# hd2.net
KiCad netlist of a schematic drawn in EAGLE
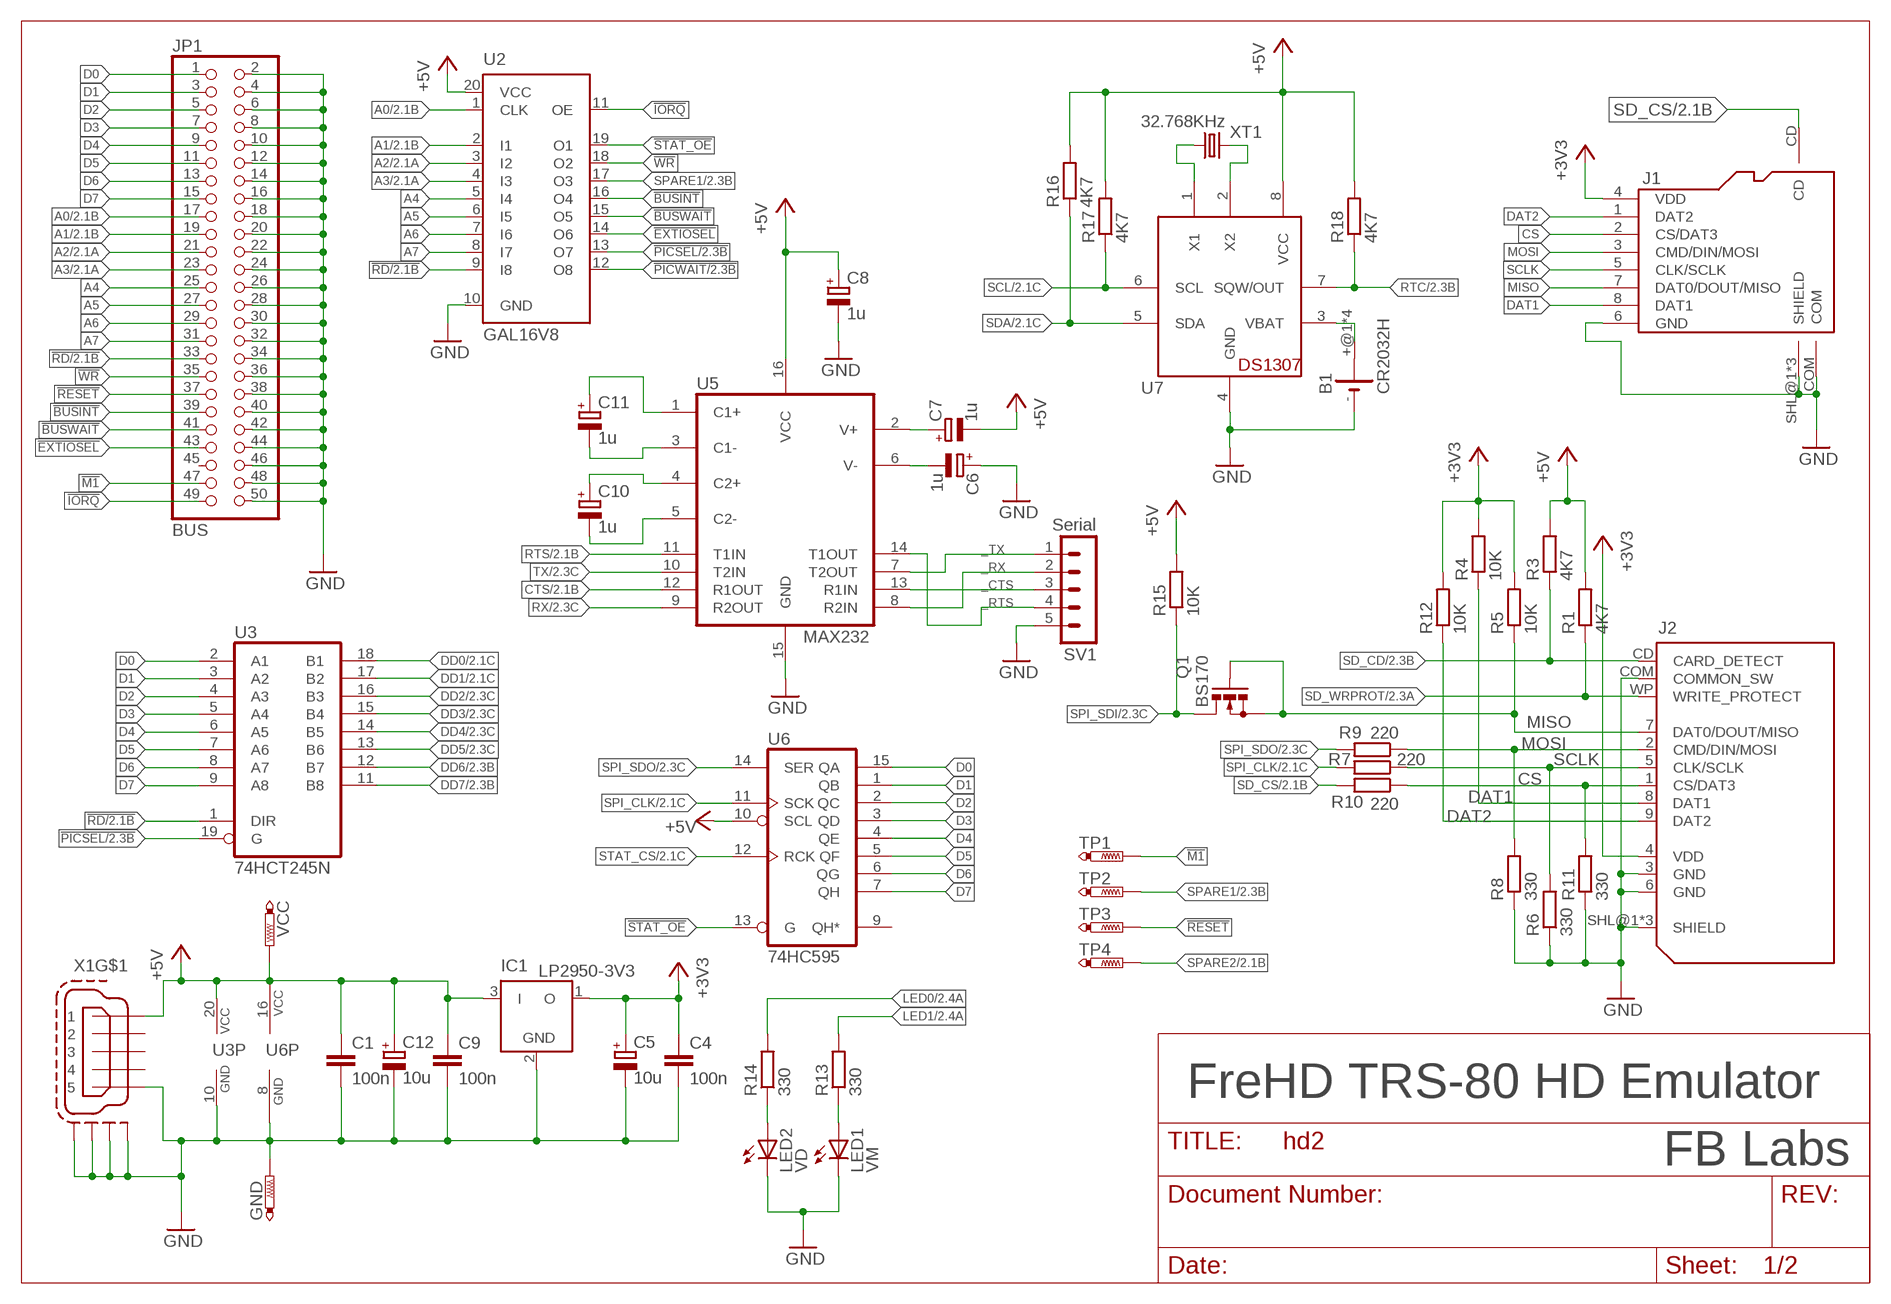
[diagram p0: schematic, sheet 1]
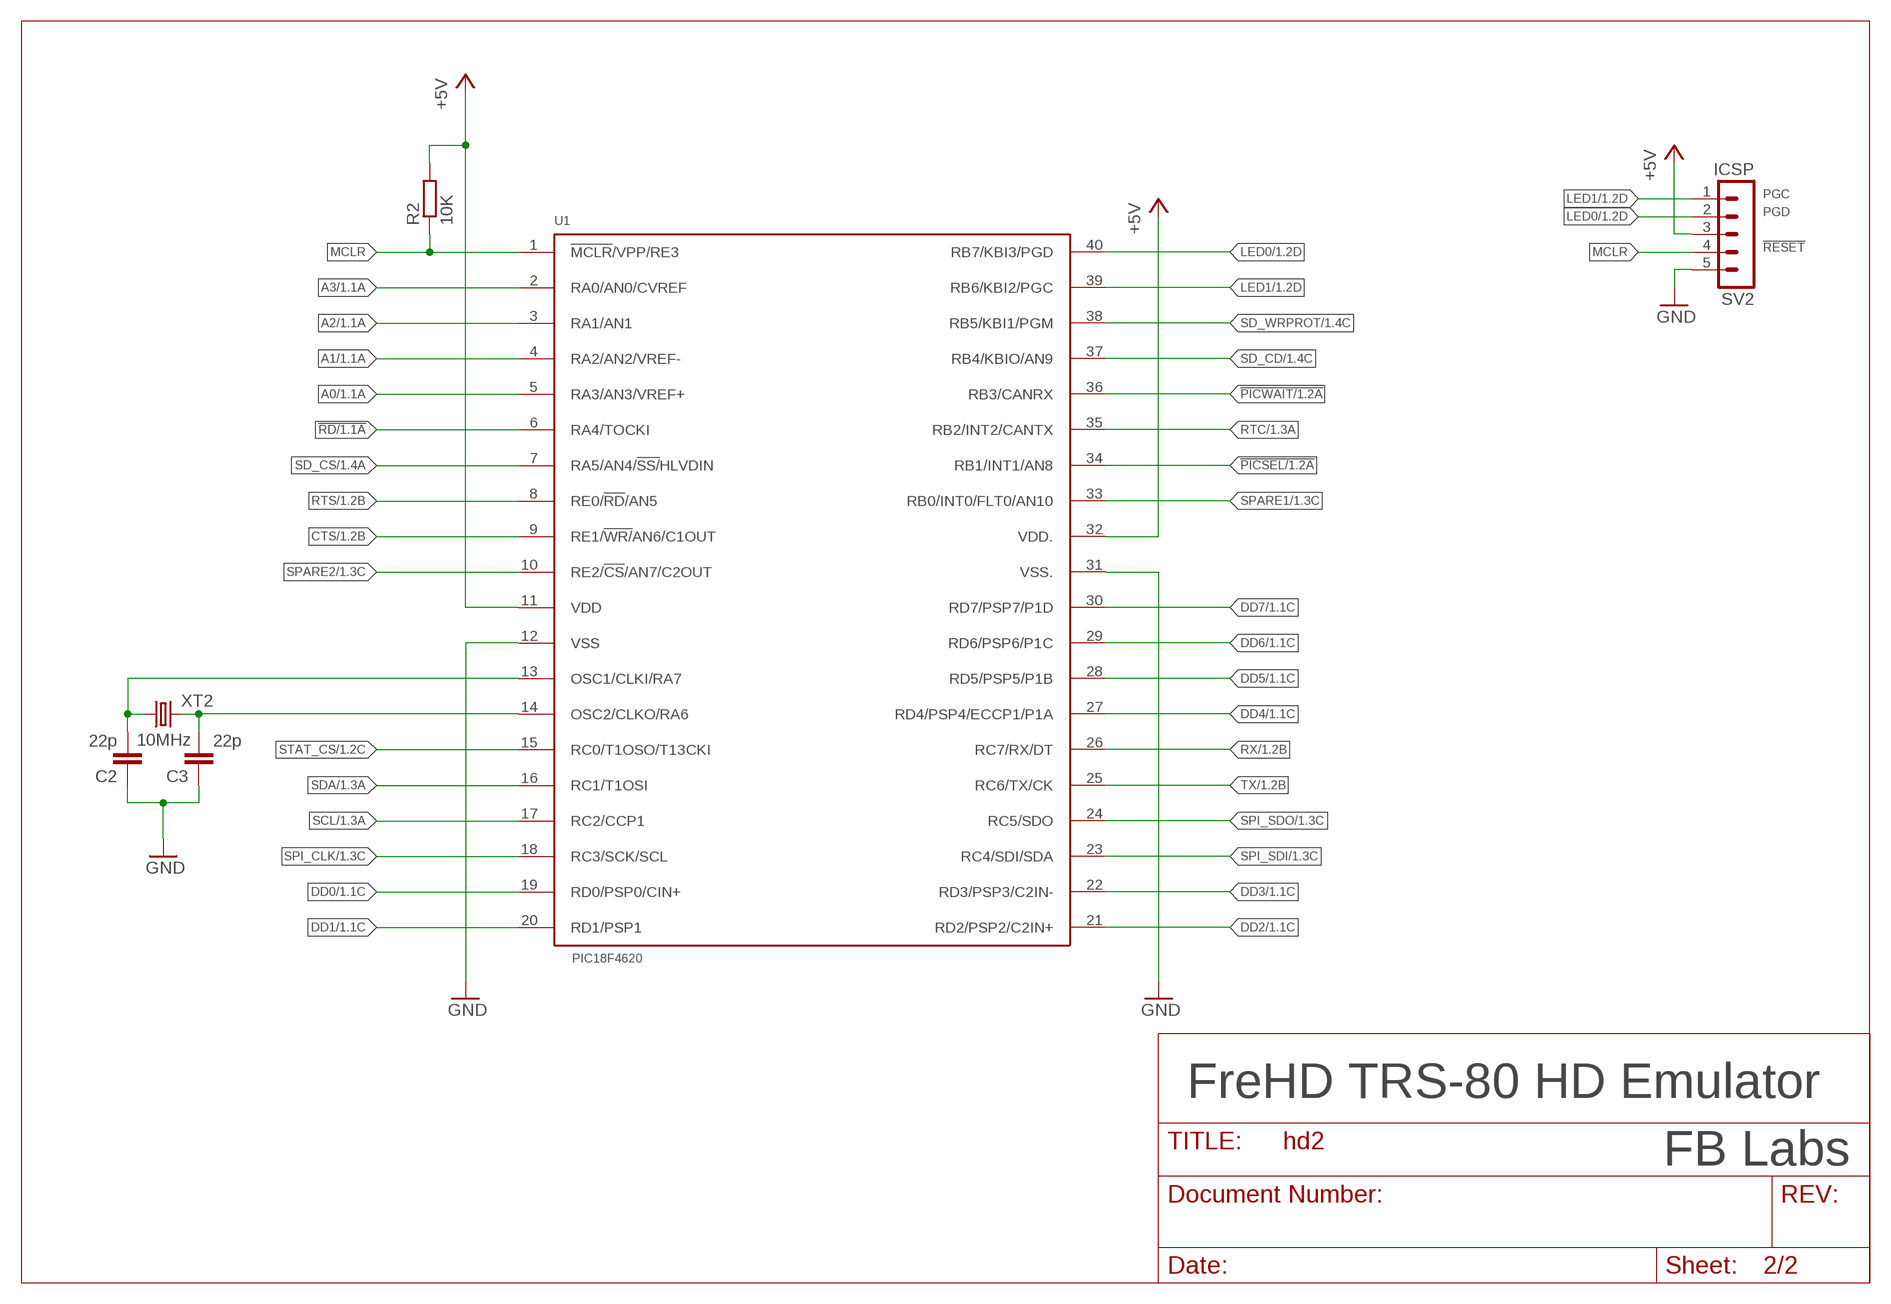
[diagram p1: schematic, sheet 2]

(export (version "E")
  (design (tool "Eeschema 10.0.6"))
  (components
    (comp (ref "B1")
      (value "CR2032H")
      (footprint "eagle-import:CR2032H")
      (libsource (lib "eagle-import") (part "CR2032H"))
    )
    (comp (ref "C1")
      (value "100n")
      (footprint "eagle-import:C050-024X044")
      (libsource (lib "eagle-import") (part "C-EU050-024X044"))
    )
    (comp (ref "C4")
      (value "100n")
      (footprint "eagle-import:C050-024X044")
      (libsource (lib "eagle-import") (part "C-EU050-024X044"))
    )
    (comp (ref "C5")
      (value "10u")
      (footprint "eagle-import:E2-4")
      (libsource (lib "eagle-import") (part "CPOL-EUE2-4"))
    )
    (comp (ref "C6")
      (value "1u")
      (footprint "eagle-import:E2-4")
      (libsource (lib "eagle-import") (part "CPOL-EUE2-4"))
    )
    (comp (ref "C7")
      (value "1u")
      (footprint "eagle-import:E2-4")
      (libsource (lib "eagle-import") (part "CPOL-EUE2-4"))
    )
    (comp (ref "C8")
      (value "1u")
      (footprint "eagle-import:E2-4")
      (libsource (lib "eagle-import") (part "CPOL-EUE2-4"))
    )
    (comp (ref "C9")
      (value "100n")
      (footprint "eagle-import:C050-024X044")
      (libsource (lib "eagle-import") (part "C-EU050-024X044"))
    )
    (comp (ref "C10")
      (value "1u")
      (footprint "eagle-import:E2-4")
      (libsource (lib "eagle-import") (part "CPOL-EUE2-4"))
    )
    (comp (ref "C11")
      (value "1u")
      (footprint "eagle-import:E2-4")
      (libsource (lib "eagle-import") (part "CPOL-EUE2-4"))
    )
    (comp (ref "C12")
      (value "10u")
      (footprint "eagle-import:E2-4")
      (libsource (lib "eagle-import") (part "CPOL-EUE2-4"))
    )
    (comp (ref "GND")
      (value "PTR1B2,54")
      (footprint "eagle-import:B2,54")
      (libsource (lib "eagle-import") (part "PTR1B2,54"))
    )
    (comp (ref "IC1")
      (value "LP2950-3V3")
      (footprint "eagle-import:TO92")
      (libsource (lib "eagle-import") (part "LP2950Z"))
    )
    (comp (ref "J1")
      (value "MICROSD-9P")
      (footprint "eagle-import:9P-SMD-W_-RING")
      (libsource (lib "eagle-import") (part "MICROSD-9P"))
    )
    (comp (ref "J2")
      (value "SDMMC06132")
      (footprint "eagle-import:06132")
      (libsource (lib "eagle-import") (part "SDMMC06132"))
    )
    (comp (ref "JP1")
      (value "BUS")
      (footprint "eagle-import:2X25")
      (libsource (lib "eagle-import") (part "PINHD-2X25"))
    )
    (comp (ref "LED1")
      (value "VM")
      (footprint "eagle-import:LED3MM")
      (libsource (lib "eagle-import") (part "LED3MM"))
    )
    (comp (ref "LED2")
      (value "VD")
      (footprint "eagle-import:LED3MM")
      (libsource (lib "eagle-import") (part "LED3MM"))
    )
    (comp (ref "Q1")
      (value "BS170")
      (footprint "eagle-import:SOT54E")
      (libsource (lib "eagle-import") (part "BS170"))
    )
    (comp (ref "R1")
      (value "4K7")
      (footprint "eagle-import:0207_10")
      (libsource (lib "eagle-import") (part "R-EU_0207/10"))
    )
    (comp (ref "R3")
      (value "4K7")
      (footprint "eagle-import:0207_10")
      (libsource (lib "eagle-import") (part "R-EU_0207/10"))
    )
    (comp (ref "R4")
      (value "10K")
      (footprint "eagle-import:0207_10")
      (libsource (lib "eagle-import") (part "R-EU_0207/10"))
    )
    (comp (ref "R5")
      (value "10K")
      (footprint "eagle-import:0207_10")
      (libsource (lib "eagle-import") (part "R-EU_0207/10"))
    )
    (comp (ref "R6")
      (value "330")
      (footprint "eagle-import:0207_10")
      (libsource (lib "eagle-import") (part "R-EU_0207/10"))
    )
    (comp (ref "R7")
      (value "220")
      (footprint "eagle-import:0207_10")
      (libsource (lib "eagle-import") (part "R-EU_0207/10"))
    )
    (comp (ref "R8")
      (value "330")
      (footprint "eagle-import:0207_10")
      (libsource (lib "eagle-import") (part "R-EU_0207/10"))
    )
    (comp (ref "R9")
      (value "220")
      (footprint "eagle-import:0207_10")
      (libsource (lib "eagle-import") (part "R-EU_0207/10"))
    )
    (comp (ref "R10")
      (value "220")
      (footprint "eagle-import:0207_10")
      (libsource (lib "eagle-import") (part "R-EU_0207/10"))
    )
    (comp (ref "R11")
      (value "330")
      (footprint "eagle-import:0207_10")
      (libsource (lib "eagle-import") (part "R-EU_0207/10"))
    )
    (comp (ref "R12")
      (value "10K")
      (footprint "eagle-import:0207_10")
      (libsource (lib "eagle-import") (part "R-EU_0207/10"))
    )
    (comp (ref "R13")
      (value "330")
      (footprint "eagle-import:0207_10")
      (libsource (lib "eagle-import") (part "R-EU_0207/10"))
    )
    (comp (ref "R14")
      (value "330")
      (footprint "eagle-import:0207_10")
      (libsource (lib "eagle-import") (part "R-EU_0207/10"))
    )
    (comp (ref "R15")
      (value "10K")
      (footprint "eagle-import:0207_10")
      (libsource (lib "eagle-import") (part "R-EU_0207/10"))
    )
    (comp (ref "R16")
      (value "4K7")
      (footprint "eagle-import:0207_10")
      (libsource (lib "eagle-import") (part "R-EU_0207/10"))
    )
    (comp (ref "R17")
      (value "4K7")
      (footprint "eagle-import:0207_10")
      (libsource (lib "eagle-import") (part "R-EU_0207/10"))
    )
    (comp (ref "R18")
      (value "4K7")
      (footprint "eagle-import:0207_10")
      (libsource (lib "eagle-import") (part "R-EU_0207/10"))
    )
    (comp (ref "SV1")
      (value "Serial")
      (footprint "eagle-import:MA05-1")
      (libsource (lib "eagle-import") (part "MA05-1"))
    )
    (comp (ref "TP1")
      (value "PTR1PAD1-10")
      (footprint "eagle-import:P1-10")
      (libsource (lib "eagle-import") (part "PTR1PAD1-10"))
    )
    (comp (ref "TP2")
      (value "PTR1PAD1-10")
      (footprint "eagle-import:P1-10")
      (libsource (lib "eagle-import") (part "PTR1PAD1-10"))
    )
    (comp (ref "TP3")
      (value "PTR1PAD1-10")
      (footprint "eagle-import:P1-10")
      (libsource (lib "eagle-import") (part "PTR1PAD1-10"))
    )
    (comp (ref "TP4")
      (value "PTR1PAD1-10")
      (footprint "eagle-import:P1-10")
      (libsource (lib "eagle-import") (part "PTR1PAD1-10"))
    )
    (comp (ref "U2")
      (value "GAL16V8")
      (footprint "eagle-import:DIL20")
      (fields (field (name "MPN") "ATF16V8CZ-15PU"))
      (libsource (lib "eagle-import") (part "ATF16V8BP3"))
    )
    (comp (ref "U3")
      (value "74HCT245N")
      (footprint "eagle-import:DIL20")
      (libsource (lib "eagle-import") (part "74245NHCT"))
    )
    (comp (ref "U5")
      (value "MAX232")
      (footprint "eagle-import:DIL16")
      (libsource (lib "eagle-import") (part "MAX232PTH"))
    )
    (comp (ref "U6")
      (value "74HC595")
      (footprint "eagle-import:DIL16")
      (libsource (lib "eagle-import") (part "74595NLS"))
    )
    (comp (ref "U7")
      (value "DS1307")
      (footprint "eagle-import:DIL08")
      (libsource (lib "eagle-import") (part "DS1307"))
    )
    (comp (ref "VCC")
      (value "PTR1B2,54")
      (footprint "eagle-import:B2,54")
      (libsource (lib "eagle-import") (part "PTR1B2,54"))
    )
    (comp (ref "X1")
      (value "MINI-USB-SCHIELD-32005-301")
      (footprint "eagle-import:32005-301")
      (libsource (lib "eagle-import") (part "MINI-USB-SCHIELD-32005-301"))
    )
    (comp (ref "XT1")
      (value "32.768KHz")
      (footprint "eagle-import:TC26V")
      (libsource (lib "eagle-import") (part "CRYSTALTC26V"))
    )
    (comp (ref "C2")
      (value "22p")
      (footprint "eagle-import:C050-024X044")
      (libsource (lib "eagle-import") (part "C-EU050-024X044"))
    )
    (comp (ref "C3")
      (value "22p")
      (footprint "eagle-import:C050-024X044")
      (libsource (lib "eagle-import") (part "C-EU050-024X044"))
    )
    (comp (ref "R2")
      (value "10K")
      (footprint "eagle-import:0207_10")
      (libsource (lib "eagle-import") (part "R-EU_0207/10"))
    )
    (comp (ref "SV2")
      (value "ICSP")
      (footprint "eagle-import:MA05-1")
      (libsource (lib "eagle-import") (part "MA05-1"))
    )
    (comp (ref "U1")
      (value "PIC18F4620")
      (footprint "eagle-import:PDIP-40")
      (libsource (lib "eagle-import") (part "PIC18F4680"))
    )
    (comp (ref "XT2")
      (value "10MHz")
      (footprint "eagle-import:HC49U-V")
      (libsource (lib "eagle-import") (part "CRYSTALHC49U-V"))
    )
  )
  (nets
    (net (code "1") (name "+3V3") (class "Default")
      (node (ref "C4") (pin "1") (pinfunction "1_1") (pintype "passive"))
      (node (ref "C5") (pin "+") (pinfunction "+_+") (pintype "passive"))
      (node (ref "IC1") (pin "1") (pinfunction "O_1") (pintype "input"))
      (node (ref "J1") (pin "4") (pinfunction "VDD_4") (pintype "power_in"))
      (node (ref "J2") (pin "4") (pinfunction "VDD_4") (pintype "power_in"))
      (node (ref "R12") (pin "2") (pinfunction "2_2") (pintype "passive"))
      (node (ref "R4") (pin "2") (pinfunction "2_2") (pintype "passive"))
      (node (ref "R5") (pin "2") (pinfunction "2_2") (pintype "passive"))
    )
    (net (code "2") (name "+5V") (class "Default")
      (node (ref "C1") (pin "1") (pinfunction "1_1") (pintype "passive"))
      (node (ref "C12") (pin "+") (pinfunction "+_+") (pintype "passive"))
      (node (ref "C7") (pin "-") (pinfunction "-_-") (pintype "passive"))
      (node (ref "C8") (pin "+") (pinfunction "+_+") (pintype "passive"))
      (node (ref "C9") (pin "1") (pinfunction "1_1") (pintype "passive"))
      (node (ref "IC1") (pin "3") (pinfunction "I_3") (pintype "input"))
      (node (ref "R1") (pin "2") (pinfunction "2_2") (pintype "passive"))
      (node (ref "R15") (pin "2") (pinfunction "2_2") (pintype "passive"))
      (node (ref "R16") (pin "2") (pinfunction "2_2") (pintype "passive"))
      (node (ref "R17") (pin "2") (pinfunction "2_2") (pintype "passive"))
      (node (ref "R18") (pin "2") (pinfunction "2_2") (pintype "passive"))
      (node (ref "R2") (pin "2") (pinfunction "2_2") (pintype "passive"))
      (node (ref "R3") (pin "2") (pinfunction "2_2") (pintype "passive"))
      (node (ref "SV2") (pin "3") (pinfunction "3_3") (pintype "passive"))
      (node (ref "U1") (pin "11") (pinfunction "VDD_11") (pintype "power_in"))
      (node (ref "U1") (pin "32") (pinfunction "VDD._32") (pintype "power_in"))
      (node (ref "U2") (pin "20") (pinfunction "VCC_20") (pintype "power_in"))
      (node (ref "U3") (pin "20") (pinfunction "VCC_20") (pintype "power_in"))
      (node (ref "U5") (pin "16") (pinfunction "VCC_16") (pintype "bidirectional"))
      (node (ref "U6") (pin "10") (pinfunction "SCL_10") (pintype "input"))
      (node (ref "U6") (pin "16") (pinfunction "VCC_16") (pintype "power_in"))
      (node (ref "U7") (pin "8") (pinfunction "VCC_8") (pintype "power_in"))
      (node (ref "VCC") (pin "TP") (pinfunction "TP_TP") (pintype "input"))
      (node (ref "X1") (pin "1") (pinfunction "1_1") (pintype "passive"))
    )
    (net (code "3") (name "A0") (class "Default")
      (node (ref "JP1") (pin "17") (pinfunction "17_17") (pintype "passive"))
      (node (ref "U1") (pin "5") (pinfunction "RA3/AN3/VREF+_5") (pintype "bidirectional"))
      (node (ref "U2") (pin "1") (pinfunction "CLK_1") (pintype "input"))
    )
    (net (code "4") (name "A1") (class "Default")
      (node (ref "JP1") (pin "19") (pinfunction "19_19") (pintype "passive"))
      (node (ref "U1") (pin "4") (pinfunction "RA2/AN2/VREF-_4") (pintype "bidirectional"))
      (node (ref "U2") (pin "2") (pinfunction "I1_2") (pintype "input"))
    )
    (net (code "5") (name "A2") (class "Default")
      (node (ref "JP1") (pin "21") (pinfunction "21_21") (pintype "passive"))
      (node (ref "U1") (pin "3") (pinfunction "RA1/AN1_3") (pintype "bidirectional"))
      (node (ref "U2") (pin "3") (pinfunction "I2_3") (pintype "input"))
    )
    (net (code "6") (name "A3") (class "Default")
      (node (ref "JP1") (pin "23") (pinfunction "23_23") (pintype "passive"))
      (node (ref "U1") (pin "2") (pinfunction "RA0/AN0/CVREF_2") (pintype "bidirectional"))
      (node (ref "U2") (pin "4") (pinfunction "I3_4") (pintype "input"))
    )
    (net (code "7") (name "A4") (class "Default")
      (node (ref "JP1") (pin "25") (pinfunction "25_25") (pintype "passive"))
      (node (ref "U2") (pin "5") (pinfunction "I4_5") (pintype "input"))
    )
    (net (code "8") (name "A5") (class "Default")
      (node (ref "JP1") (pin "27") (pinfunction "27_27") (pintype "passive"))
      (node (ref "U2") (pin "6") (pinfunction "I5_6") (pintype "input"))
    )
    (net (code "9") (name "A6") (class "Default")
      (node (ref "JP1") (pin "29") (pinfunction "29_29") (pintype "passive"))
      (node (ref "U2") (pin "7") (pinfunction "I6_7") (pintype "input"))
    )
    (net (code "10") (name "A7") (class "Default")
      (node (ref "JP1") (pin "31") (pinfunction "31_31") (pintype "passive"))
      (node (ref "U2") (pin "8") (pinfunction "I7_8") (pintype "input"))
    )
    (net (code "11") (name "CS") (class "Default")
      (node (ref "J1") (pin "2") (pinfunction "CS/DAT3_2") (pintype "input"))
      (node (ref "J2") (pin "1") (pinfunction "CS/DAT3_1") (pintype "input"))
      (node (ref "R10") (pin "1") (pinfunction "1_1") (pintype "passive"))
      (node (ref "R11") (pin "2") (pinfunction "2_2") (pintype "passive"))
    )
    (net (code "12") (name "CTS") (class "Default")
      (node (ref "U1") (pin "9") (pinfunction "RE1/~{WR/}AN6/C1OUT_9") (pintype "bidirectional"))
      (node (ref "U5") (pin "12") (pinfunction "R1OUT_12") (pintype "output"))
    )
    (net (code "13") (name "D0") (class "Default")
      (node (ref "JP1") (pin "1") (pinfunction "1_1") (pintype "passive"))
      (node (ref "U3") (pin "2") (pinfunction "A1_2") (pintype "bidirectional"))
      (node (ref "U6") (pin "15") (pinfunction "QA_15") (pintype "tri_state"))
    )
    (net (code "14") (name "D1") (class "Default")
      (node (ref "JP1") (pin "3") (pinfunction "3_3") (pintype "passive"))
      (node (ref "U3") (pin "3") (pinfunction "A2_3") (pintype "bidirectional"))
      (node (ref "U6") (pin "1") (pinfunction "QB_1") (pintype "tri_state"))
    )
    (net (code "15") (name "D2") (class "Default")
      (node (ref "JP1") (pin "5") (pinfunction "5_5") (pintype "passive"))
      (node (ref "U3") (pin "4") (pinfunction "A3_4") (pintype "bidirectional"))
      (node (ref "U6") (pin "2") (pinfunction "QC_2") (pintype "tri_state"))
    )
    (net (code "16") (name "D3") (class "Default")
      (node (ref "JP1") (pin "7") (pinfunction "7_7") (pintype "passive"))
      (node (ref "U3") (pin "5") (pinfunction "A4_5") (pintype "bidirectional"))
      (node (ref "U6") (pin "3") (pinfunction "QD_3") (pintype "tri_state"))
    )
    (net (code "17") (name "D4") (class "Default")
      (node (ref "JP1") (pin "9") (pinfunction "9_9") (pintype "passive"))
      (node (ref "U3") (pin "6") (pinfunction "A5_6") (pintype "bidirectional"))
      (node (ref "U6") (pin "4") (pinfunction "QE_4") (pintype "tri_state"))
    )
    (net (code "18") (name "D5") (class "Default")
      (node (ref "JP1") (pin "11") (pinfunction "11_11") (pintype "passive"))
      (node (ref "U3") (pin "7") (pinfunction "A6_7") (pintype "bidirectional"))
      (node (ref "U6") (pin "5") (pinfunction "QF_5") (pintype "tri_state"))
    )
    (net (code "19") (name "D6") (class "Default")
      (node (ref "JP1") (pin "13") (pinfunction "13_13") (pintype "passive"))
      (node (ref "U3") (pin "8") (pinfunction "A7_8") (pintype "bidirectional"))
      (node (ref "U6") (pin "6") (pinfunction "QG_6") (pintype "tri_state"))
    )
    (net (code "20") (name "D7") (class "Default")
      (node (ref "JP1") (pin "15") (pinfunction "15_15") (pintype "passive"))
      (node (ref "U3") (pin "9") (pinfunction "A8_9") (pintype "bidirectional"))
      (node (ref "U6") (pin "7") (pinfunction "QH_7") (pintype "tri_state"))
    )
    (net (code "21") (name "DAT1") (class "Default")
      (node (ref "J1") (pin "8") (pinfunction "DAT1_8") (pintype "bidirectional"))
      (node (ref "J2") (pin "8") (pinfunction "DAT1_8") (pintype "bidirectional"))
      (node (ref "R4") (pin "1") (pinfunction "1_1") (pintype "passive"))
    )
    (net (code "22") (name "DAT2") (class "Default")
      (node (ref "J1") (pin "1") (pinfunction "DAT2_1") (pintype "bidirectional"))
      (node (ref "J2") (pin "9") (pinfunction "DAT2_9") (pintype "bidirectional"))
      (node (ref "R12") (pin "1") (pinfunction "1_1") (pintype "passive"))
    )
    (net (code "23") (name "DD0") (class "Default")
      (node (ref "U1") (pin "19") (pinfunction "RD0/PSP0/CIN+_19") (pintype "bidirectional"))
      (node (ref "U3") (pin "18") (pinfunction "B1_18") (pintype "bidirectional"))
    )
    (net (code "24") (name "DD1") (class "Default")
      (node (ref "U1") (pin "20") (pinfunction "RD1/PSP1_20") (pintype "bidirectional"))
      (node (ref "U3") (pin "17") (pinfunction "B2_17") (pintype "bidirectional"))
    )
    (net (code "25") (name "DD2") (class "Default")
      (node (ref "U1") (pin "21") (pinfunction "RD2/PSP2/C2IN+_21") (pintype "bidirectional"))
      (node (ref "U3") (pin "16") (pinfunction "B3_16") (pintype "bidirectional"))
    )
    (net (code "26") (name "DD3") (class "Default")
      (node (ref "U1") (pin "22") (pinfunction "RD3/PSP3/C2IN-_22") (pintype "bidirectional"))
      (node (ref "U3") (pin "15") (pinfunction "B4_15") (pintype "bidirectional"))
    )
    (net (code "27") (name "DD4") (class "Default")
      (node (ref "U1") (pin "27") (pinfunction "RD4/PSP4/ECCP1/P1A_27") (pintype "bidirectional"))
      (node (ref "U3") (pin "14") (pinfunction "B5_14") (pintype "bidirectional"))
    )
    (net (code "28") (name "DD5") (class "Default")
      (node (ref "U1") (pin "28") (pinfunction "RD5/PSP5/P1B_28") (pintype "bidirectional"))
      (node (ref "U3") (pin "13") (pinfunction "B6_13") (pintype "bidirectional"))
    )
    (net (code "29") (name "DD6") (class "Default")
      (node (ref "U1") (pin "29") (pinfunction "RD6/PSP6/P1C_29") (pintype "bidirectional"))
      (node (ref "U3") (pin "12") (pinfunction "B7_12") (pintype "bidirectional"))
    )
    (net (code "30") (name "DD7") (class "Default")
      (node (ref "U1") (pin "30") (pinfunction "RD7/PSP7/P1D_30") (pintype "bidirectional"))
      (node (ref "U3") (pin "11") (pinfunction "B8_11") (pintype "bidirectional"))
    )
    (net (code "31") (name "GND") (class "Default")
      (node (ref "B1") (pin "-") (pinfunction "-_-") (pintype "passive"))
      (node (ref "C1") (pin "2") (pinfunction "2_2") (pintype "passive"))
      (node (ref "C12") (pin "-") (pinfunction "-_-") (pintype "passive"))
      (node (ref "C2") (pin "1") (pinfunction "1_1") (pintype "passive"))
      (node (ref "C3") (pin "1") (pinfunction "1_1") (pintype "passive"))
      (node (ref "C4") (pin "2") (pinfunction "2_2") (pintype "passive"))
      (node (ref "C5") (pin "-") (pinfunction "-_-") (pintype "passive"))
      (node (ref "C6") (pin "+") (pinfunction "+_+") (pintype "passive"))
      (node (ref "C8") (pin "-") (pinfunction "-_-") (pintype "passive"))
      (node (ref "C9") (pin "2") (pinfunction "2_2") (pintype "passive"))
      (node (ref "GND") (pin "TP") (pinfunction "TP_TP") (pintype "input"))
      (node (ref "IC1") (pin "2") (pinfunction "GND_2") (pintype "power_in"))
      (node (ref "J1") (pin "6") (pinfunction "GND_6") (pintype "power_in"))
      (node (ref "J1") (pin "COM") (pinfunction "COM_COM") (pintype "passive"))
      (node (ref "J1") (pin "SHL@1") (pinfunction "SHIELD_SHL@1") (pintype "power_in"))
      (node (ref "J1") (pin "SHL@2") (pinfunction "SHIELD_SHL@2") (pintype "power_in"))
      (node (ref "J1") (pin "SHL@3") (pinfunction "SHIELD_SHL@3") (pintype "power_in"))
      (node (ref "J2") (pin "3") (pinfunction "GND_3") (pintype "power_in"))
      (node (ref "J2") (pin "6") (pinfunction "GND_6") (pintype "power_in"))
      (node (ref "J2") (pin "COM") (pinfunction "COMMON_SW_COM") (pintype "passive"))
      (node (ref "J2") (pin "SHL@1") (pinfunction "SHIELD_SHL@1") (pintype "power_in"))
      (node (ref "J2") (pin "SHL@2") (pinfunction "SHIELD_SHL@2") (pintype "power_in"))
      (node (ref "J2") (pin "SHL@3") (pinfunction "SHIELD_SHL@3") (pintype "power_in"))
      (node (ref "JP1") (pin "10") (pinfunction "10_10") (pintype "passive"))
      (node (ref "JP1") (pin "12") (pinfunction "12_12") (pintype "passive"))
      (node (ref "JP1") (pin "14") (pinfunction "14_14") (pintype "passive"))
      (node (ref "JP1") (pin "16") (pinfunction "16_16") (pintype "passive"))
      (node (ref "JP1") (pin "18") (pinfunction "18_18") (pintype "passive"))
      (node (ref "JP1") (pin "2") (pinfunction "2_2") (pintype "passive"))
      (node (ref "JP1") (pin "20") (pinfunction "20_20") (pintype "passive"))
      (node (ref "JP1") (pin "22") (pinfunction "22_22") (pintype "passive"))
      (node (ref "JP1") (pin "24") (pinfunction "24_24") (pintype "passive"))
      (node (ref "JP1") (pin "26") (pinfunction "26_26") (pintype "passive"))
      (node (ref "JP1") (pin "28") (pinfunction "28_28") (pintype "passive"))
      (node (ref "JP1") (pin "30") (pinfunction "30_30") (pintype "passive"))
      (node (ref "JP1") (pin "32") (pinfunction "32_32") (pintype "passive"))
      (node (ref "JP1") (pin "34") (pinfunction "34_34") (pintype "passive"))
      (node (ref "JP1") (pin "36") (pinfunction "36_36") (pintype "passive"))
      (node (ref "JP1") (pin "38") (pinfunction "38_38") (pintype "passive"))
      (node (ref "JP1") (pin "4") (pinfunction "4_4") (pintype "passive"))
      (node (ref "JP1") (pin "40") (pinfunction "40_40") (pintype "passive"))
      (node (ref "JP1") (pin "42") (pinfunction "42_42") (pintype "passive"))
      (node (ref "JP1") (pin "44") (pinfunction "44_44") (pintype "passive"))
      (node (ref "JP1") (pin "46") (pinfunction "46_46") (pintype "passive"))
      (node (ref "JP1") (pin "48") (pinfunction "48_48") (pintype "passive"))
      (node (ref "JP1") (pin "50") (pinfunction "50_50") (pintype "passive"))
      (node (ref "JP1") (pin "6") (pinfunction "6_6") (pintype "passive"))
      (node (ref "JP1") (pin "8") (pinfunction "8_8") (pintype "passive"))
      (node (ref "LED1") (pin "K") (pinfunction "C_K") (pintype "passive"))
      (node (ref "LED2") (pin "K") (pinfunction "C_K") (pintype "passive"))
      (node (ref "R11") (pin "1") (pinfunction "1_1") (pintype "passive"))
      (node (ref "R6") (pin "1") (pinfunction "1_1") (pintype "passive"))
      (node (ref "R8") (pin "1") (pinfunction "1_1") (pintype "passive"))
      (node (ref "SV1") (pin "5") (pinfunction "5_5") (pintype "passive"))
      (node (ref "SV2") (pin "5") (pinfunction "5_5") (pintype "passive"))
      (node (ref "U1") (pin "12") (pinfunction "VSS_12") (pintype "power_in"))
      (node (ref "U1") (pin "31") (pinfunction "VSS._31") (pintype "power_in"))
      (node (ref "U2") (pin "10") (pinfunction "GND_10") (pintype "power_in"))
      (node (ref "U3") (pin "10") (pinfunction "GND_10") (pintype "power_in"))
      (node (ref "U5") (pin "15") (pinfunction "GND_15") (pintype "bidirectional"))
      (node (ref "U6") (pin "8") (pinfunction "GND_8") (pintype "power_in"))
      (node (ref "U7") (pin "4") (pinfunction "GND_4") (pintype "power_in"))
      (node (ref "X1") (pin "5") (pinfunction "5_5") (pintype "passive"))
      (node (ref "X1") (pin "M1") (pinfunction "S1_M1") (pintype "passive"))
      (node (ref "X1") (pin "M2") (pinfunction "S2_M2") (pintype "passive"))
      (node (ref "X1") (pin "M3") (pinfunction "S3_M3") (pintype "passive"))
      (node (ref "X1") (pin "M4") (pinfunction "S4_M4") (pintype "passive"))
    )
    (net (code "32") (name "LED0") (class "Default")
      (node (ref "R14") (pin "2") (pinfunction "2_2") (pintype "passive"))
      (node (ref "SV2") (pin "2") (pinfunction "2_2") (pintype "passive"))
      (node (ref "U1") (pin "40") (pinfunction "RB7/KBI3/PGD_40") (pintype "bidirectional"))
    )
    (net (code "33") (name "LED1") (class "Default")
      (node (ref "R13") (pin "2") (pinfunction "2_2") (pintype "passive"))
      (node (ref "SV2") (pin "1") (pinfunction "1_1") (pintype "passive"))
      (node (ref "U1") (pin "39") (pinfunction "RB6/KBI2/PGC_39") (pintype "bidirectional"))
    )
    (net (code "34") (name "MCLR") (class "Default")
      (node (ref "R2") (pin "1") (pinfunction "1_1") (pintype "passive"))
      (node (ref "SV2") (pin "4") (pinfunction "4_4") (pintype "passive"))
      (node (ref "U1") (pin "1") (pinfunction "~{MCLR}/VPP/RE3_1") (pintype "power_in"))
    )
    (net (code "35") (name "MISO") (class "Default")
      (node (ref "J1") (pin "7") (pinfunction "DAT0/DOUT/MISO_7") (pintype "output"))
      (node (ref "J2") (pin "7") (pinfunction "DAT0/DOUT/MISO_7") (pintype "output"))
      (node (ref "Q1") (pin "G") (pinfunction "G_G") (pintype "passive"))
      (node (ref "Q1") (pin "S") (pinfunction "S_S") (pintype "passive"))
      (node (ref "R5") (pin "1") (pinfunction "1_1") (pintype "passive"))
    )
    (net (code "36") (name "MOSI") (class "Default")
      (node (ref "J1") (pin "3") (pinfunction "CMD/DIN/MOSI_3") (pintype "input"))
      (node (ref "J2") (pin "2") (pinfunction "CMD/DIN/MOSI_2") (pintype "input"))
      (node (ref "R8") (pin "2") (pinfunction "2_2") (pintype "passive"))
      (node (ref "R9") (pin "1") (pinfunction "1_1") (pintype "passive"))
    )
    (net (code "37") (name "Net-(LED1-PadA)") (class "Default")
      (node (ref "LED1") (pin "A") (pinfunction "A_A") (pintype "passive"))
      (node (ref "R13") (pin "1") (pinfunction "1_1") (pintype "passive"))
    )
    (net (code "38") (name "Net-(LED2-PadA)") (class "Default")
      (node (ref "LED2") (pin "A") (pinfunction "A_A") (pintype "passive"))
      (node (ref "R14") (pin "1") (pinfunction "1_1") (pintype "passive"))
    )
    (net (code "39") (name "Net-(U1-OSC1{slash}CLKI{slash}RA7)") (class "Default")
      (node (ref "C2") (pin "2") (pinfunction "2_2") (pintype "passive"))
      (node (ref "U1") (pin "13") (pinfunction "OSC1/CLKI/RA7_13") (pintype "input"))
      (node (ref "XT2") (pin "1") (pinfunction "1_1") (pintype "passive"))
    )
    (net (code "40") (name "Net-(U1-OSC2{slash}CLKO{slash}RA6)") (class "Default")
      (node (ref "C3") (pin "2") (pinfunction "2_2") (pintype "passive"))
      (node (ref "U1") (pin "14") (pinfunction "OSC2/CLKO/RA6_14") (pintype "bidirectional"))
      (node (ref "XT2") (pin "2") (pinfunction "2_2") (pintype "passive"))
    )
    (net (code "41") (name "Net-(U5-C1+)") (class "Default")
      (node (ref "C11") (pin "+") (pinfunction "+_+") (pintype "passive"))
      (node (ref "U5") (pin "1") (pinfunction "C1+_1") (pintype "bidirectional"))
    )
    (net (code "42") (name "Net-(U5-C1-)") (class "Default")
      (node (ref "C11") (pin "-") (pinfunction "-_-") (pintype "passive"))
      (node (ref "U5") (pin "3") (pinfunction "C1-_3") (pintype "bidirectional"))
    )
    (net (code "43") (name "Net-(U5-C2+)") (class "Default")
      (node (ref "C10") (pin "+") (pinfunction "+_+") (pintype "passive"))
      (node (ref "U5") (pin "4") (pinfunction "C2+_4") (pintype "bidirectional"))
    )
    (net (code "44") (name "Net-(U5-C2-)") (class "Default")
      (node (ref "C10") (pin "-") (pinfunction "-_-") (pintype "passive"))
      (node (ref "U5") (pin "5") (pinfunction "C2-_5") (pintype "bidirectional"))
    )
    (net (code "45") (name "Net-(U5-V+)") (class "Default")
      (node (ref "C7") (pin "+") (pinfunction "+_+") (pintype "passive"))
      (node (ref "U5") (pin "2") (pinfunction "V+_2") (pintype "bidirectional"))
    )
    (net (code "46") (name "Net-(U5-V-)") (class "Default")
      (node (ref "C6") (pin "-") (pinfunction "-_-") (pintype "passive"))
      (node (ref "U5") (pin "6") (pinfunction "V-_6") (pintype "bidirectional"))
    )
    (net (code "47") (name "Net-(U7-VBAT)") (class "Default")
      (node (ref "B1") (pin "+@1") (pinfunction "+_+@1") (pintype "passive"))
      (node (ref "B1") (pin "+@2") (pinfunction "+_+@2") (pintype "passive"))
      (node (ref "B1") (pin "+@3") (pinfunction "+_+@3") (pintype "passive"))
      (node (ref "B1") (pin "+@4") (pinfunction "+_+@4") (pintype "passive"))
      (node (ref "U7") (pin "3") (pinfunction "VBAT_3") (pintype "power_in"))
    )
    (net (code "48") (name "Net-(U7-X1)") (class "Default")
      (node (ref "U7") (pin "1") (pinfunction "X1_1") (pintype "passive"))
      (node (ref "XT1") (pin "1") (pinfunction "1_1") (pintype "passive"))
    )
    (net (code "49") (name "Net-(U7-X2)") (class "Default")
      (node (ref "U7") (pin "2") (pinfunction "X2_2") (pintype "passive"))
      (node (ref "XT1") (pin "2") (pinfunction "2_2") (pintype "passive"))
    )
    (net (code "50") (name "RTC") (class "Default")
      (node (ref "R18") (pin "1") (pinfunction "1_1") (pintype "passive"))
      (node (ref "U1") (pin "35") (pinfunction "RB2/INT2/CANTX_35") (pintype "bidirectional"))
      (node (ref "U7") (pin "7") (pinfunction "SQW/OUT_7") (pintype "bidirectional"))
    )
    (net (code "51") (name "RTS") (class "Default")
      (node (ref "U1") (pin "8") (pinfunction "RE0/~{RD}/AN5_8") (pintype "bidirectional"))
      (node (ref "U5") (pin "11") (pinfunction "T1IN_11") (pintype "input"))
    )
    (net (code "52") (name "RX") (class "Default")
      (node (ref "U1") (pin "26") (pinfunction "RC7/RX/DT_26") (pintype "bidirectional"))
      (node (ref "U5") (pin "9") (pinfunction "R2OUT_9") (pintype "output"))
    )
    (net (code "53") (name "SCL") (class "Default")
      (node (ref "R17") (pin "1") (pinfunction "1_1") (pintype "passive"))
      (node (ref "U1") (pin "17") (pinfunction "RC2/CCP1_17") (pintype "bidirectional"))
      (node (ref "U7") (pin "6") (pinfunction "SCL_6") (pintype "bidirectional"))
    )
    (net (code "54") (name "SCLK") (class "Default")
      (node (ref "J1") (pin "5") (pinfunction "CLK/SCLK_5") (pintype "input"))
      (node (ref "J2") (pin "5") (pinfunction "CLK/SCLK_5") (pintype "input"))
      (node (ref "R6") (pin "2") (pinfunction "2_2") (pintype "passive"))
      (node (ref "R7") (pin "1") (pinfunction "1_1") (pintype "passive"))
    )
    (net (code "55") (name "SDA") (class "Default")
      (node (ref "R16") (pin "1") (pinfunction "1_1") (pintype "passive"))
      (node (ref "U1") (pin "16") (pinfunction "RC1/T1OSI_16") (pintype "bidirectional"))
      (node (ref "U7") (pin "5") (pinfunction "SDA_5") (pintype "bidirectional"))
    )
    (net (code "56") (name "SD_CD") (class "Default")
      (node (ref "J2") (pin "CD") (pinfunction "CARD_DETECT_CD") (pintype "passive"))
      (node (ref "R3") (pin "1") (pinfunction "1_1") (pintype "passive"))
      (node (ref "U1") (pin "37") (pinfunction "RB4/KBIO/AN9_37") (pintype "bidirectional"))
    )
    (net (code "57") (name "SD_CS") (class "Default")
      (node (ref "J1") (pin "CD") (pinfunction "CD_CD") (pintype "passive"))
      (node (ref "R10") (pin "2") (pinfunction "2_2") (pintype "passive"))
      (node (ref "U1") (pin "7") (pinfunction "RA5/AN4/~{SS/}HLVDIN_7") (pintype "bidirectional"))
    )
    (net (code "58") (name "SD_WRPROT") (class "Default")
      (node (ref "J2") (pin "WP") (pinfunction "WRITE_PROTECT_WP") (pintype "passive"))
      (node (ref "R1") (pin "1") (pinfunction "1_1") (pintype "passive"))
      (node (ref "U1") (pin "38") (pinfunction "RB5/KBI1/PGM_38") (pintype "bidirectional"))
    )
    (net (code "59") (name "SPARE1") (class "Default")
      (node (ref "TP2") (pin "TP") (pinfunction "TP_TP") (pintype "input"))
      (node (ref "U1") (pin "33") (pinfunction "RB0/INT0/FLT0/AN10_33") (pintype "bidirectional"))
      (node (ref "U2") (pin "17") (pinfunction "O3_17") (pintype "output"))
    )
    (net (code "60") (name "SPARE2") (class "Default")
      (node (ref "TP4") (pin "TP") (pinfunction "TP_TP") (pintype "input"))
      (node (ref "U1") (pin "10") (pinfunction "RE2/~{CS}/AN7/C2OUT_10") (pintype "bidirectional"))
    )
    (net (code "61") (name "SPI_CLK") (class "Default")
      (node (ref "R7") (pin "2") (pinfunction "2_2") (pintype "passive"))
      (node (ref "U1") (pin "18") (pinfunction "RC3/SCK/SCL_18") (pintype "bidirectional"))
      (node (ref "U6") (pin "11") (pinfunction "SCK_11") (pintype "input"))
    )
    (net (code "62") (name "SPI_SDI") (class "Default")
      (node (ref "Q1") (pin "D") (pinfunction "D_D") (pintype "passive"))
      (node (ref "R15") (pin "1") (pinfunction "1_1") (pintype "passive"))
      (node (ref "U1") (pin "23") (pinfunction "RC4/SDI/SDA_23") (pintype "bidirectional"))
    )
    (net (code "63") (name "SPI_SDO") (class "Default")
      (node (ref "R9") (pin "2") (pinfunction "2_2") (pintype "passive"))
      (node (ref "U1") (pin "24") (pinfunction "RC5/SDO_24") (pintype "bidirectional"))
      (node (ref "U6") (pin "14") (pinfunction "SER_14") (pintype "input"))
    )
    (net (code "64") (name "STAT_CS") (class "Default")
      (node (ref "U1") (pin "15") (pinfunction "RC0/T1OSO/T13CKI_15") (pintype "bidirectional"))
      (node (ref "U6") (pin "12") (pinfunction "RCK_12") (pintype "input"))
    )
    (net (code "65") (name "TX") (class "Default")
      (node (ref "U1") (pin "25") (pinfunction "RC6/TX/CK_25") (pintype "bidirectional"))
      (node (ref "U5") (pin "10") (pinfunction "T2IN_10") (pintype "input"))
    )
    (net (code "66") (name "_CTS") (class "Default")
      (node (ref "SV1") (pin "3") (pinfunction "3_3") (pintype "passive"))
      (node (ref "U5") (pin "13") (pinfunction "R1IN_13") (pintype "input"))
    )
    (net (code "67") (name "_RTS") (class "Default")
      (node (ref "SV1") (pin "4") (pinfunction "4_4") (pintype "passive"))
      (node (ref "U5") (pin "14") (pinfunction "T1OUT_14") (pintype "output"))
    )
    (net (code "68") (name "_RX") (class "Default")
      (node (ref "SV1") (pin "2") (pinfunction "2_2") (pintype "passive"))
      (node (ref "U5") (pin "8") (pinfunction "R2IN_8") (pintype "input"))
    )
    (net (code "69") (name "_TX") (class "Default")
      (node (ref "SV1") (pin "1") (pinfunction "1_1") (pintype "passive"))
      (node (ref "U5") (pin "7") (pinfunction "T2OUT_7") (pintype "output"))
    )
    (net (code "70") (name "unconnected-(JP1-Pad45)") (class "Default")
      (node (ref "JP1") (pin "45") (pinfunction "45_45") (pintype "passive"))
    )
    (net (code "71") (name "unconnected-(U6A-QH*-Pad9)") (class "Default")
      (node (ref "U6") (pin "9") (pinfunction "QH*_9") (pintype "tri_state"))
    )
    (net (code "72") (name "unconnected-(X1-Pad2)") (class "Default")
      (node (ref "X1") (pin "2") (pinfunction "2_2") (pintype "passive"))
    )
    (net (code "73") (name "unconnected-(X1-Pad3)") (class "Default")
      (node (ref "X1") (pin "3") (pinfunction "3_3") (pintype "passive"))
    )
    (net (code "74") (name "unconnected-(X1-Pad4)") (class "Default")
      (node (ref "X1") (pin "4") (pinfunction "4_4") (pintype "passive"))
    )
    (net (code "75") (name "~{BUSINT}") (class "Default")
      (node (ref "JP1") (pin "39") (pinfunction "39_39") (pintype "passive"))
      (node (ref "U2") (pin "16") (pinfunction "O4_16") (pintype "output"))
    )
    (net (code "76") (name "~{BUSWAIT}") (class "Default")
      (node (ref "JP1") (pin "41") (pinfunction "41_41") (pintype "passive"))
      (node (ref "U2") (pin "15") (pinfunction "O5_15") (pintype "output"))
    )
    (net (code "77") (name "~{EXTIOSEL}") (class "Default")
      (node (ref "JP1") (pin "43") (pinfunction "43_43") (pintype "passive"))
      (node (ref "U2") (pin "14") (pinfunction "O6_14") (pintype "output"))
    )
    (net (code "78") (name "~{IORQ}") (class "Default")
      (node (ref "JP1") (pin "49") (pinfunction "49_49") (pintype "passive"))
      (node (ref "U2") (pin "11") (pinfunction "OE_11") (pintype "input"))
    )
    (net (code "79") (name "~{M1}") (class "Default")
      (node (ref "JP1") (pin "47") (pinfunction "47_47") (pintype "passive"))
      (node (ref "TP1") (pin "TP") (pinfunction "TP_TP") (pintype "input"))
    )
    (net (code "80") (name "~{PICSEL}") (class "Default")
      (node (ref "U1") (pin "34") (pinfunction "RB1/INT1/AN8_34") (pintype "bidirectional"))
      (node (ref "U2") (pin "13") (pinfunction "O7_13") (pintype "output"))
      (node (ref "U3") (pin "19") (pinfunction "G_19") (pintype "input"))
    )
    (net (code "81") (name "~{PICWAIT}") (class "Default")
      (node (ref "U1") (pin "36") (pinfunction "RB3/CANRX_36") (pintype "bidirectional"))
      (node (ref "U2") (pin "12") (pinfunction "O8_12") (pintype "output"))
    )
    (net (code "82") (name "~{RD}") (class "Default")
      (node (ref "JP1") (pin "33") (pinfunction "33_33") (pintype "passive"))
      (node (ref "U1") (pin "6") (pinfunction "RA4/TOCKI_6") (pintype "bidirectional"))
      (node (ref "U2") (pin "9") (pinfunction "I8_9") (pintype "input"))
      (node (ref "U3") (pin "1") (pinfunction "DIR_1") (pintype "input"))
    )
    (net (code "83") (name "~{RESET}") (class "Default")
      (node (ref "JP1") (pin "37") (pinfunction "37_37") (pintype "passive"))
      (node (ref "TP3") (pin "TP") (pinfunction "TP_TP") (pintype "input"))
    )
    (net (code "84") (name "~{STAT_OE}") (class "Default")
      (node (ref "U2") (pin "19") (pinfunction "O1_19") (pintype "output"))
      (node (ref "U6") (pin "13") (pinfunction "G_13") (pintype "input"))
    )
    (net (code "85") (name "~{WR}") (class "Default")
      (node (ref "JP1") (pin "35") (pinfunction "35_35") (pintype "passive"))
      (node (ref "U2") (pin "18") (pinfunction "O2_18") (pintype "output"))
    )
  )
)
